# VOLT_REGULATION.net
KiCad netlist of a schematic drawn in Altium Designer
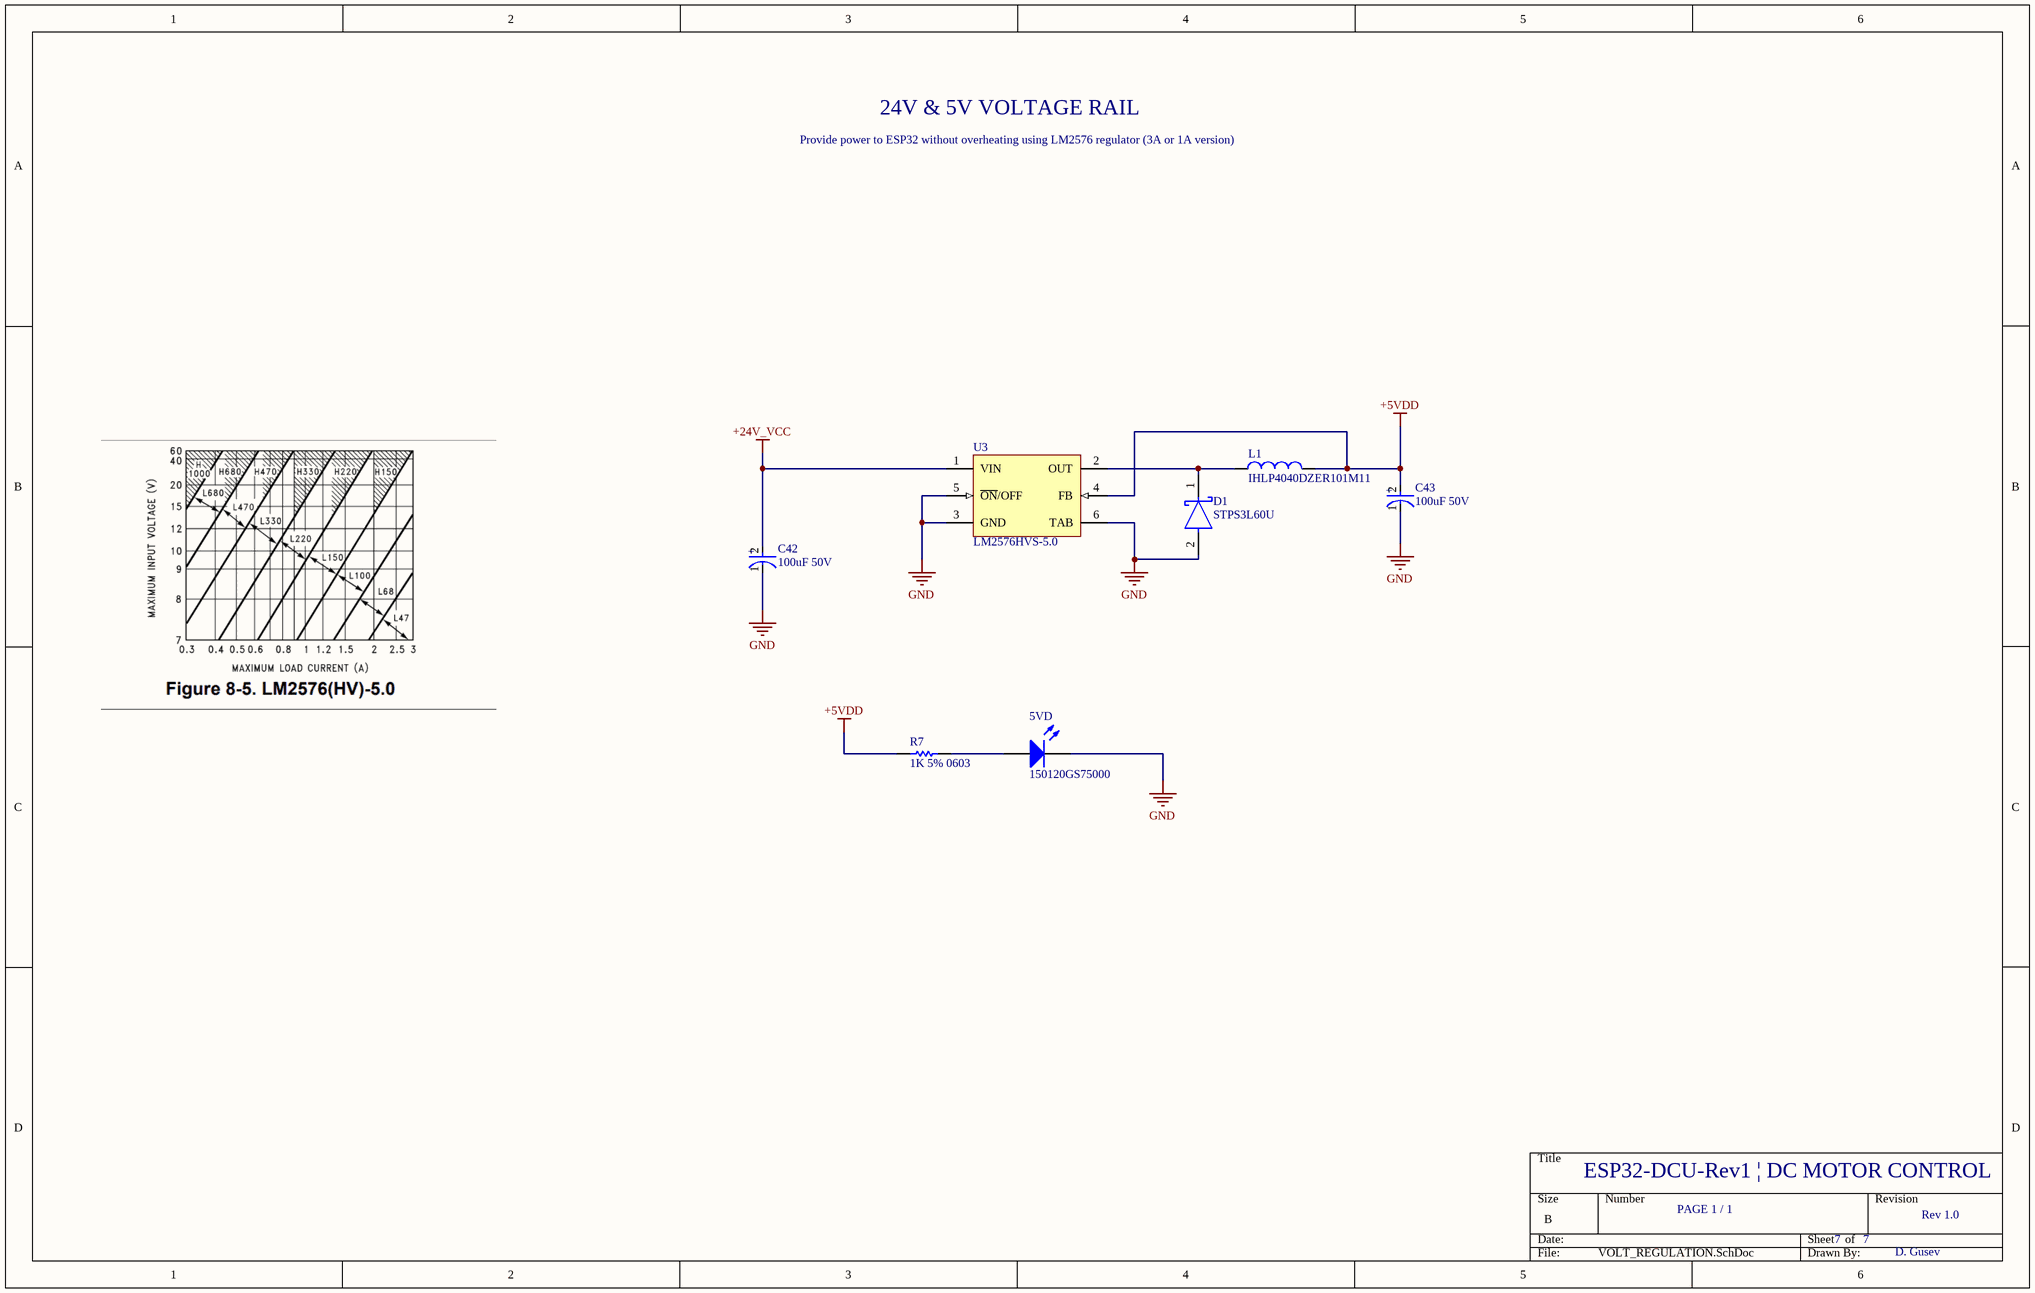
[diagram p0: VOLT_REGULATION.SchDoc]

(export (version "E")
  (design (tool "Eeschema 10.0.6"))
  (components
    (comp (ref "5VD")
      (value "150120GS75000")
      (footprint "1206_A")
      (description "SMD mono-color Chip LED, WL-SMCW, Green")
      (fields (field (name "MANUFACTURER") "Wuerth Elektronik"))
      (libsource (lib "Altium Content Vault") (part "WE-LED_K1A2-2"))
    )
    (comp (ref "C42")
      (value "100uF 50V")
      (footprint "FP-EEE-FK1H101P-MFG")
      (description "CAP ALUM 100UF 20% 50V SMD")
      (fields (field (name "TOLERANCE") "20%") (field (name "MANUFACTURER PART NUMBER") "EEE-FK1H101P"))
      (libsource (lib "Altium Content Vault") (part "cf48714ba7e38822c1575c7ec0b6d1f"))
    )
    (comp (ref "C43")
      (value "100uF 50V")
      (footprint "FP-EEE-FK1H101P-MFG")
      (description "CAP ALUM 100UF 20% 50V SMD")
      (fields (field (name "TOLERANCE") "20%") (field (name "MANUFACTURER PART NUMBER") "EEE-FK1H101P"))
      (libsource (lib "Altium Content Vault") (part "cf48714ba7e38822c1575c7ec0b6d1f"))
    )
    (comp (ref "D1")
      (value "STPS3L60U")
      (footprint "FP-SMB-MFG")
      (description "DIODE SCHOTTKY 60V 3A SMB")
      (fields
        (field (name "OCTOPART") "https://octopart.com/stps3l60u-stmicroelectronics-334329")
        (field (name "MANUFACTURER") "STMicroelectronics")
      )
      (libsource (lib "Altium Content Vault") (part "fefb30dabb5d097ae2f038500735429"))
    )
    (comp (ref "L1")
      (value "IHLP4040DZER101M11")
      (footprint "VISH-IHLP4040DZER101M11_V")
      (fields (field (name "MANUFACTURER") "Vishay") (field (name "TOLERANCE") "20%"))
      (libsource (lib "Altium Content Vault") (part "IND-2"))
    )
    (comp (ref "R7")
      (value "1K 5% 0603")
      (footprint "RESC1608X55X25NL10T15")
      (description "Chip Resistor, 1 KOhm, +/-1%, 0.1 W, -55 to 155 degC, 0603 (1608 Metric), RoHS, Tape and Reel")
      (fields (field (name "MANUFACTURER") "Yageo"))
      (libsource (lib "Altium Content Vault") (part "RES-2"))
    )
    (comp (ref "U3")
      (value "LM2576HVS-5.0")
      (footprint "KTT0005B_L")
      (description "SIMPLE SWITCHER® 3A Step-Down Voltage Regulator, 5-pin TO-263")
      (fields (field (name "MANUFACTURER") "Texas Instruments"))
      (libsource (lib "Altium Content Vault") (part "PM-REG-LM2575HVS-12"))
    )
  )
  (nets
    (net (code "1") (name "+5VDD") (class "Default")
      (node (ref "C43") (pin "2") (pinfunction "A_2") (pintype "passive"))
      (node (ref "L1") (pin "2") (pinfunction "2_2") (pintype "passive"))
      (node (ref "R7") (pin "1") (pinfunction "1_1") (pintype "passive"))
      (node (ref "U3") (pin "4") (pinfunction "FB_4") (pintype "input"))
    )
    (net (code "2") (name "+24V_VCC") (class "Default")
      (node (ref "C42") (pin "2") (pinfunction "A_2") (pintype "passive"))
      (node (ref "U3") (pin "1") (pinfunction "VIN_1") (pintype "power_in"))
    )
    (net (code "3") (name "GND") (class "Default")
      (node (ref "5VD") (pin "1") (pinfunction "K_1") (pintype "passive"))
      (node (ref "C42") (pin "1") (pinfunction "C_1") (pintype "passive"))
      (node (ref "C43") (pin "1") (pinfunction "C_1") (pintype "passive"))
      (node (ref "D1") (pin "2") (pinfunction "A_2") (pintype "passive"))
      (node (ref "U3") (pin "3") (pinfunction "GND_3") (pintype "power_in"))
      (node (ref "U3") (pin "5") (pinfunction "~{ON}/OFF_5") (pintype "input"))
      (node (ref "U3") (pin "6") (pinfunction "TAB_6") (pintype "power_in"))
    )
    (net (code "4") (name "Net-(5VD-A)") (class "Default")
      (node (ref "5VD") (pin "2") (pinfunction "A_2") (pintype "passive"))
      (node (ref "R7") (pin "2") (pinfunction "2_2") (pintype "passive"))
    )
    (net (code "5") (name "Net-(D1-K)") (class "Default")
      (node (ref "D1") (pin "1") (pinfunction "K_1") (pintype "passive"))
      (node (ref "L1") (pin "1") (pinfunction "1_1") (pintype "passive"))
      (node (ref "U3") (pin "2") (pinfunction "OUT_2") (pintype "power_in"))
    )
  )
)
